# SpaceInvaders-OtherMill-BottomOnly.net
KiCad netlist of a schematic drawn in EAGLE
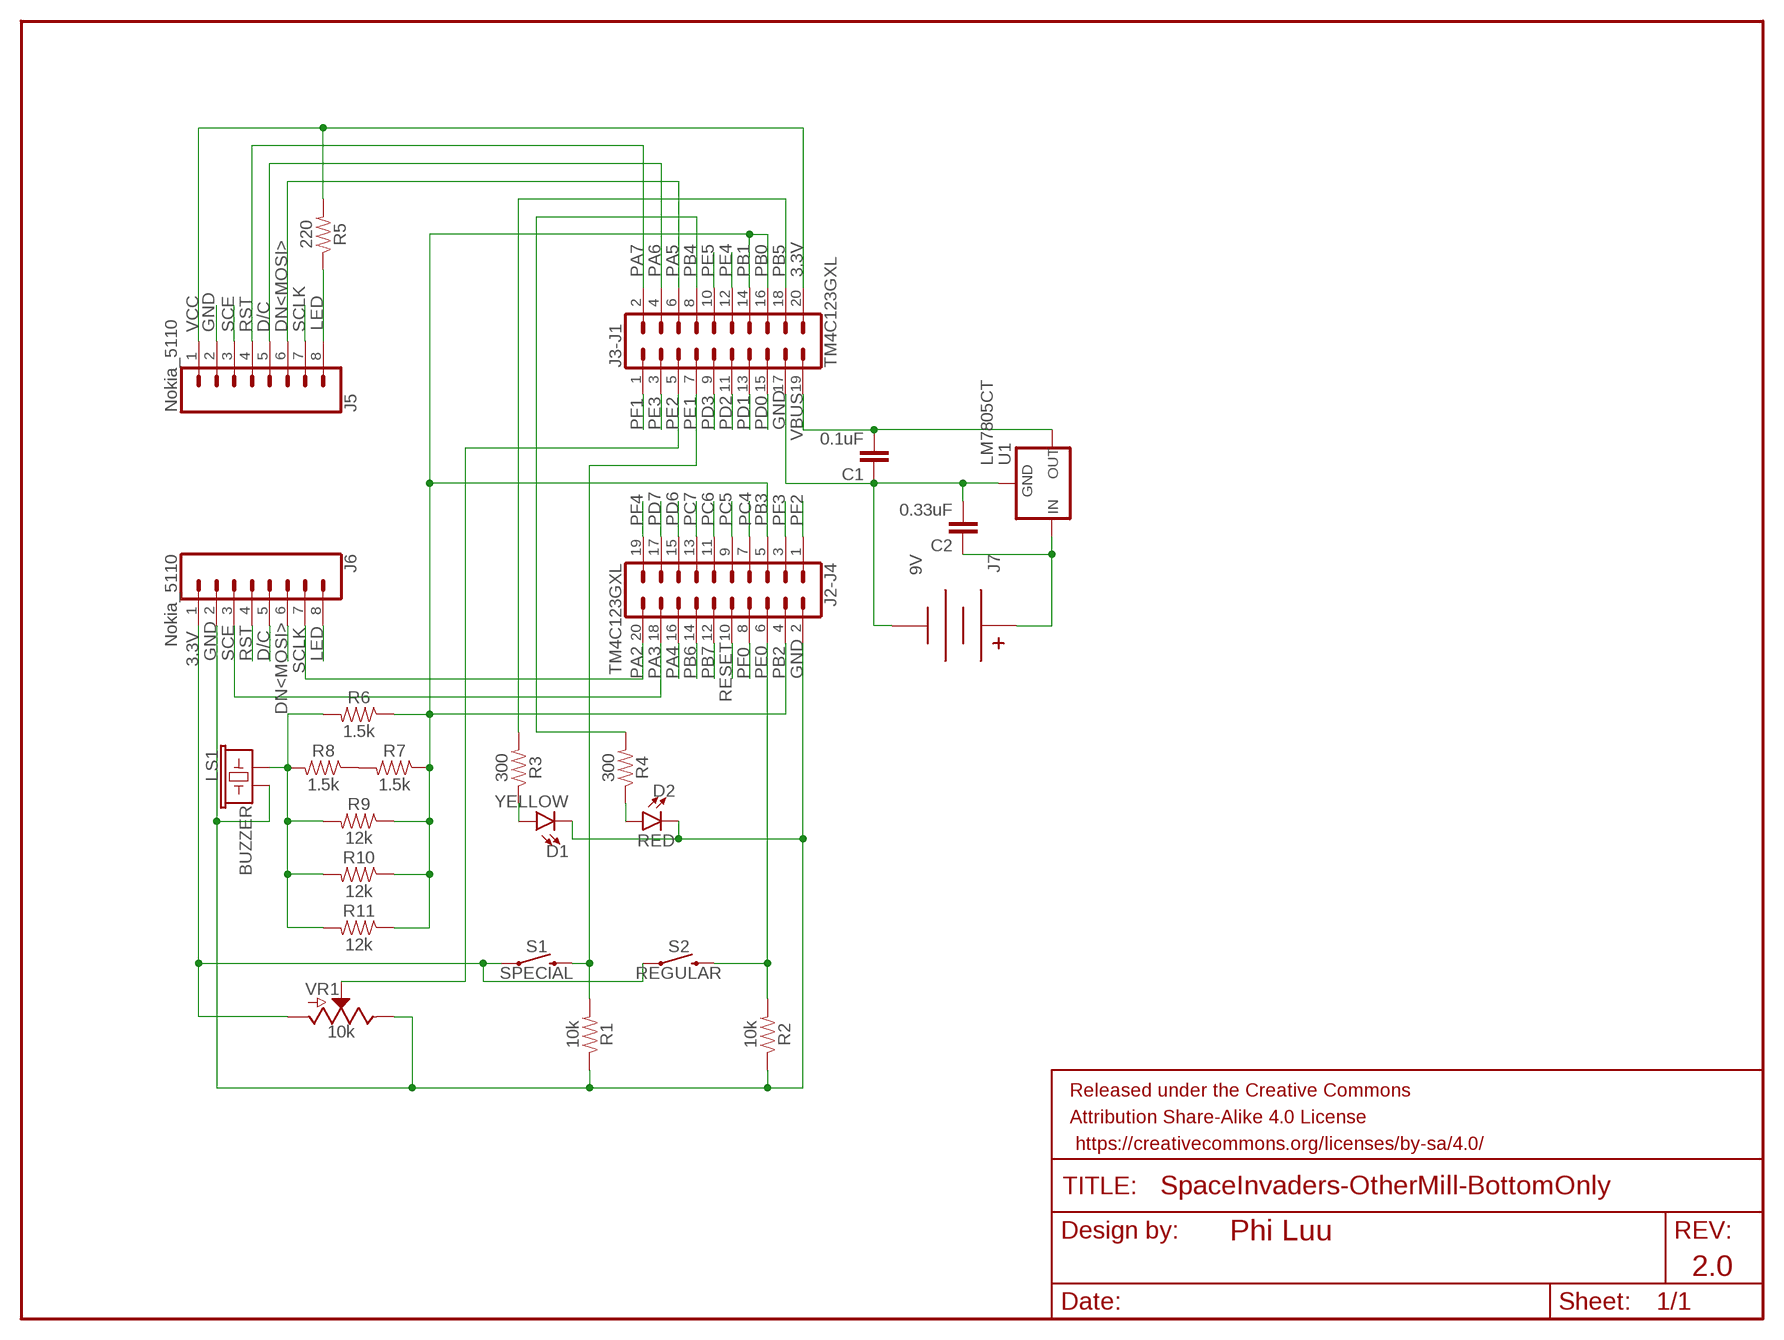
[diagram p0: schematic, sheet 1]

(export (version "E")
  (design (tool "Eeschema 10.0.6"))
  (components
    (comp (ref "C1")
      (value "0.1uF")
      (footprint "eagle-import:CAP-PTH-SMALL-KIT")
      (libsource (lib "eagle-import") (part "0.1UF-KIT-EZ-50V-20%"))
    )
    (comp (ref "C2")
      (value "0.33uF")
      (footprint "eagle-import:CAP-PTH-SMALL-KIT")
      (libsource (lib "eagle-import") (part "0.1UF-KIT-EZ-50V-20%"))
    )
    (comp (ref "D1")
      (value "YELLOW")
      (footprint "eagle-import:LED_5MM")
      (libsource (lib "eagle-import") (part "LED5MM"))
    )
    (comp (ref "D2")
      (value "RED")
      (footprint "eagle-import:LED_5MM")
      (libsource (lib "eagle-import") (part "LED5MM"))
    )
    (comp (ref "FRAME1")
      (value "FRAME-LETTER")
      (footprint "eagle-import:CREATIVE_COMMONS")
      (libsource (lib "eagle-import") (part "FRAME-LETTER"))
    )
    (comp (ref "J2-J4")
      (value "TM4C123GXL")
      (footprint "eagle-import:2X10")
      (libsource (lib "eagle-import") (part "CONN_10X2"))
    )
    (comp (ref "J3-J1")
      (value "TM4C123GXL")
      (footprint "eagle-import:2X10")
      (libsource (lib "eagle-import") (part "CONN_10X2"))
    )
    (comp (ref "J5")
      (value "Nokia_5110")
      (footprint "eagle-import:1X08")
      (libsource (lib "eagle-import") (part "CONN_08{dblquote}"))
    )
    (comp (ref "J6")
      (value "Nokia_5110")
      (footprint "eagle-import:1X08")
      (libsource (lib "eagle-import") (part "CONN_08{dblquote}"))
    )
    (comp (ref "J7")
      (value "9V")
      (footprint "eagle-import:BC9VPC")
      (libsource (lib "eagle-import") (part "BC9VPC"))
    )
    (comp (ref "LS1")
      (value "BUZZER")
      (footprint "eagle-import:BUZZER-12MM")
      (libsource (lib "eagle-import") (part "BUZZER-PTH"))
    )
    (comp (ref "R1")
      (value "10k")
      (footprint "eagle-import:AXIAL-0.3")
      (libsource (lib "eagle-import") (part "10KOHM-HORIZ-1/4W-5%"))
    )
    (comp (ref "R2")
      (value "10k")
      (footprint "eagle-import:AXIAL-0.3")
      (libsource (lib "eagle-import") (part "10KOHM-HORIZ-1/4W-5%"))
    )
    (comp (ref "R3")
      (value "300")
      (footprint "eagle-import:AXIAL-0.3")
      (libsource (lib "eagle-import") (part "1KOHM-HORIZ-1/4W-5%"))
    )
    (comp (ref "R4")
      (value "300")
      (footprint "eagle-import:AXIAL-0.3")
      (libsource (lib "eagle-import") (part "1KOHM-HORIZ-1/4W-5%"))
    )
    (comp (ref "R5")
      (value "220")
      (footprint "eagle-import:AXIAL-0.3")
      (libsource (lib "eagle-import") (part "1KOHM-HORIZ-1/4W-5%"))
    )
    (comp (ref "R6")
      (value "1.5k")
      (footprint "eagle-import:AXIAL-0.3")
      (libsource (lib "eagle-import") (part "1KOHM-HORIZ-1/4W-5%"))
    )
    (comp (ref "R7")
      (value "1.5k")
      (footprint "eagle-import:AXIAL-0.3")
      (libsource (lib "eagle-import") (part "1KOHM-HORIZ-1/4W-5%"))
    )
    (comp (ref "R8")
      (value "1.5k")
      (footprint "eagle-import:AXIAL-0.3")
      (libsource (lib "eagle-import") (part "1KOHM-HORIZ-1/4W-5%"))
    )
    (comp (ref "R9")
      (value "12k")
      (footprint "eagle-import:AXIAL-0.3")
      (libsource (lib "eagle-import") (part "1KOHM-HORIZ-1/4W-5%"))
    )
    (comp (ref "R10")
      (value "12k")
      (footprint "eagle-import:AXIAL-0.3")
      (libsource (lib "eagle-import") (part "1KOHM-HORIZ-1/4W-5%"))
    )
    (comp (ref "R11")
      (value "12k")
      (footprint "eagle-import:AXIAL-0.3")
      (libsource (lib "eagle-import") (part "1KOHM-HORIZ-1/4W-5%"))
    )
    (comp (ref "S1")
      (value "SPECIAL")
      (footprint "eagle-import:TACTILE_SWITCH_PTH_6.0MM")
      (libsource (lib "eagle-import") (part "MOMENTARY-SWITCH-SPST-PTH-6.0MM"))
    )
    (comp (ref "S2")
      (value "REGULAR")
      (footprint "eagle-import:TACTILE_SWITCH_PTH_6.0MM")
      (libsource (lib "eagle-import") (part "MOMENTARY-SWITCH-SPST-PTH-6.0MM"))
    )
    (comp (ref "U1")
      (value "LM7805CT")
      (footprint "eagle-import:TO-220-ALT")
      (libsource (lib "eagle-import") (part "V_REG_78XX-TO-220"))
    )
    (comp (ref "VR1")
      (value "10k")
      (footprint "eagle-import:SLIDER-MEDIUM")
      (libsource (lib "eagle-import") (part "POTENTIOMETER_SLIDE-30MM-1/10W-20%"))
    )
  )
  (nets
    (net (code "1") (name "/3.3V") (class "Default")
      (node (ref "J3-J1") (pin "20") (pinfunction "20_20") (pintype "passive"))
      (node (ref "J5") (pin "1") (pinfunction "1_1") (pintype "passive"))
      (node (ref "J6") (pin "1") (pinfunction "1_1") (pintype "passive"))
      (node (ref "R5") (pin "P$2") (pinfunction "2_P$2") (pintype "passive"))
      (node (ref "S1") (pin "1") (pinfunction "1_1") (pintype "passive"))
      (node (ref "S2") (pin "1") (pinfunction "1_1") (pintype "passive"))
      (node (ref "VR1") (pin "BOTTOM") (pinfunction "A_BOTTOM") (pintype "passive"))
    )
    (net (code "2") (name "/DN<MOSI>") (class "Default")
      (node (ref "J6") (pin "6") (pinfunction "6_6") (pintype "passive"))
    )
    (net (code "3") (name "/D{slash}C") (class "Default")
      (node (ref "J6") (pin "5") (pinfunction "5_5") (pintype "passive"))
    )
    (net (code "4") (name "/GND") (class "Default")
      (node (ref "C1") (pin "1") (pinfunction "1_1") (pintype "passive"))
      (node (ref "C2") (pin "2") (pinfunction "2_2") (pintype "passive"))
      (node (ref "D1") (pin "K") (pinfunction "C_K") (pintype "passive"))
      (node (ref "D2") (pin "K") (pinfunction "C_K") (pintype "passive"))
      (node (ref "J2-J4") (pin "2") (pinfunction "2_2") (pintype "passive"))
      (node (ref "J3-J1") (pin "17") (pinfunction "17_17") (pintype "passive"))
      (node (ref "J5") (pin "2") (pinfunction "2_2") (pintype "passive"))
      (node (ref "J6") (pin "2") (pinfunction "2_2") (pintype "passive"))
      (node (ref "J7") (pin "V-") (pinfunction "V-_V-") (pintype "bidirectional"))
      (node (ref "LS1") (pin "-") (pinfunction "2_-") (pintype "passive"))
      (node (ref "R1") (pin "P$1") (pinfunction "1_P$1") (pintype "passive"))
      (node (ref "R2") (pin "P$1") (pinfunction "1_P$1") (pintype "passive"))
      (node (ref "U1") (pin "GND") (pinfunction "GND_GND") (pintype "input"))
      (node (ref "VR1") (pin "TOP") (pinfunction "E_TOP") (pintype "passive"))
    )
    (net (code "5") (name "/LED") (class "Default")
      (node (ref "J5") (pin "8") (pinfunction "8_8") (pintype "passive"))
      (node (ref "J6") (pin "8") (pinfunction "8_8") (pintype "passive"))
      (node (ref "R5") (pin "P$1") (pinfunction "1_P$1") (pintype "passive"))
    )
    (net (code "6") (name "/PA2") (class "Default")
      (node (ref "J2-J4") (pin "20") (pinfunction "20_20") (pintype "passive"))
      (node (ref "J6") (pin "7") (pinfunction "7_7") (pintype "passive"))
    )
    (net (code "7") (name "/PA3") (class "Default")
      (node (ref "J2-J4") (pin "18") (pinfunction "18_18") (pintype "passive"))
      (node (ref "J6") (pin "3") (pinfunction "3_3") (pintype "passive"))
    )
    (net (code "8") (name "/PA4") (class "Default")
      (node (ref "J2-J4") (pin "16") (pinfunction "16_16") (pintype "passive"))
    )
    (net (code "9") (name "/PA5") (class "Default")
      (node (ref "J3-J1") (pin "6") (pinfunction "6_6") (pintype "passive"))
      (node (ref "J5") (pin "6") (pinfunction "6_6") (pintype "passive"))
    )
    (net (code "10") (name "/PA6") (class "Default")
      (node (ref "J3-J1") (pin "4") (pinfunction "4_4") (pintype "passive"))
      (node (ref "J5") (pin "5") (pinfunction "5_5") (pintype "passive"))
    )
    (net (code "11") (name "/PA7") (class "Default")
      (node (ref "J3-J1") (pin "2") (pinfunction "2_2") (pintype "passive"))
      (node (ref "J5") (pin "4") (pinfunction "4_4") (pintype "passive"))
    )
    (net (code "12") (name "/PB2") (class "Default")
      (node (ref "J2-J4") (pin "4") (pinfunction "4_4") (pintype "passive"))
      (node (ref "J2-J4") (pin "5") (pinfunction "5_5") (pintype "passive"))
      (node (ref "J3-J1") (pin "14") (pinfunction "14_14") (pintype "passive"))
      (node (ref "J3-J1") (pin "16") (pinfunction "16_16") (pintype "passive"))
      (node (ref "R10") (pin "P$1") (pinfunction "1_P$1") (pintype "passive"))
      (node (ref "R11") (pin "P$1") (pinfunction "1_P$1") (pintype "passive"))
      (node (ref "R6") (pin "P$1") (pinfunction "1_P$1") (pintype "passive"))
      (node (ref "R7") (pin "P$1") (pinfunction "1_P$1") (pintype "passive"))
      (node (ref "R9") (pin "P$1") (pinfunction "1_P$1") (pintype "passive"))
    )
    (net (code "13") (name "/PB4") (class "Default")
      (node (ref "J3-J1") (pin "8") (pinfunction "8_8") (pintype "passive"))
      (node (ref "R4") (pin "P$2") (pinfunction "2_P$2") (pintype "passive"))
    )
    (net (code "14") (name "/PB5") (class "Default")
      (node (ref "J3-J1") (pin "18") (pinfunction "18_18") (pintype "passive"))
      (node (ref "R3") (pin "P$2") (pinfunction "2_P$2") (pintype "passive"))
    )
    (net (code "15") (name "/PB6") (class "Default")
      (node (ref "J2-J4") (pin "14") (pinfunction "14_14") (pintype "passive"))
    )
    (net (code "16") (name "/PB7") (class "Default")
      (node (ref "J2-J4") (pin "12") (pinfunction "12_12") (pintype "passive"))
    )
    (net (code "17") (name "/PC4") (class "Default")
      (node (ref "J2-J4") (pin "7") (pinfunction "7_7") (pintype "passive"))
    )
    (net (code "18") (name "/PC5") (class "Default")
      (node (ref "J2-J4") (pin "9") (pinfunction "9_9") (pintype "passive"))
    )
    (net (code "19") (name "/PC6") (class "Default")
      (node (ref "J2-J4") (pin "11") (pinfunction "11_11") (pintype "passive"))
    )
    (net (code "20") (name "/PC7") (class "Default")
      (node (ref "J2-J4") (pin "13") (pinfunction "13_13") (pintype "passive"))
    )
    (net (code "21") (name "/PD0") (class "Default")
      (node (ref "J3-J1") (pin "15") (pinfunction "15_15") (pintype "passive"))
    )
    (net (code "22") (name "/PD1") (class "Default")
      (node (ref "J3-J1") (pin "13") (pinfunction "13_13") (pintype "passive"))
    )
    (net (code "23") (name "/PD2") (class "Default")
      (node (ref "J3-J1") (pin "11") (pinfunction "11_11") (pintype "passive"))
    )
    (net (code "24") (name "/PD3") (class "Default")
      (node (ref "J3-J1") (pin "9") (pinfunction "9_9") (pintype "passive"))
    )
    (net (code "25") (name "/PD6") (class "Default")
      (node (ref "J2-J4") (pin "15") (pinfunction "15_15") (pintype "passive"))
    )
    (net (code "26") (name "/PD7") (class "Default")
      (node (ref "J2-J4") (pin "17") (pinfunction "17_17") (pintype "passive"))
    )
    (net (code "27") (name "/PE0") (class "Default")
      (node (ref "J2-J4") (pin "6") (pinfunction "6_6") (pintype "passive"))
      (node (ref "R2") (pin "P$2") (pinfunction "2_P$2") (pintype "passive"))
      (node (ref "S2") (pin "3") (pinfunction "2_3") (pintype "passive"))
    )
    (net (code "28") (name "/PE1") (class "Default")
      (node (ref "J3-J1") (pin "7") (pinfunction "7_7") (pintype "passive"))
      (node (ref "R1") (pin "P$2") (pinfunction "2_P$2") (pintype "passive"))
      (node (ref "S1") (pin "3") (pinfunction "2_3") (pintype "passive"))
    )
    (net (code "29") (name "/PE2") (class "Default")
      (node (ref "J3-J1") (pin "5") (pinfunction "5_5") (pintype "passive"))
      (node (ref "VR1") (pin "WIPER") (pinfunction "S_WIPER") (pintype "passive"))
    )
    (net (code "30") (name "/PE3") (class "Default")
      (node (ref "J3-J1") (pin "3") (pinfunction "3_3") (pintype "passive"))
    )
    (net (code "31") (name "/PE4") (class "Default")
      (node (ref "J3-J1") (pin "12") (pinfunction "12_12") (pintype "passive"))
    )
    (net (code "32") (name "/PE5") (class "Default")
      (node (ref "J3-J1") (pin "10") (pinfunction "10_10") (pintype "passive"))
    )
    (net (code "33") (name "/PF0") (class "Default")
      (node (ref "J2-J4") (pin "8") (pinfunction "8_8") (pintype "passive"))
    )
    (net (code "34") (name "/PF1") (class "Default")
      (node (ref "J3-J1") (pin "1") (pinfunction "1_1") (pintype "passive"))
    )
    (net (code "35") (name "/PF2") (class "Default")
      (node (ref "J2-J4") (pin "1") (pinfunction "1_1") (pintype "passive"))
    )
    (net (code "36") (name "/PF3") (class "Default")
      (node (ref "J2-J4") (pin "3") (pinfunction "3_3") (pintype "passive"))
    )
    (net (code "37") (name "/PF4") (class "Default")
      (node (ref "J2-J4") (pin "19") (pinfunction "19_19") (pintype "passive"))
    )
    (net (code "38") (name "/RESET") (class "Default")
      (node (ref "J2-J4") (pin "10") (pinfunction "10_10") (pintype "passive"))
    )
    (net (code "39") (name "/RST") (class "Default")
      (node (ref "J6") (pin "4") (pinfunction "4_4") (pintype "passive"))
    )
    (net (code "40") (name "/SCE") (class "Default")
      (node (ref "J5") (pin "3") (pinfunction "3_3") (pintype "passive"))
    )
    (net (code "41") (name "/SCLK") (class "Default")
      (node (ref "J5") (pin "7") (pinfunction "7_7") (pintype "passive"))
    )
    (net (code "42") (name "/VBUS") (class "Default")
      (node (ref "C1") (pin "2") (pinfunction "2_2") (pintype "passive"))
      (node (ref "J3-J1") (pin "19") (pinfunction "19_19") (pintype "passive"))
      (node (ref "U1") (pin "OUT") (pinfunction "OUT_OUT") (pintype "passive"))
    )
    (net (code "43") (name "Net-(C2-Pad1)") (class "Default")
      (node (ref "C2") (pin "1") (pinfunction "1_1") (pintype "passive"))
      (node (ref "J7") (pin "V+") (pinfunction "V+_V+") (pintype "bidirectional"))
      (node (ref "U1") (pin "IN") (pinfunction "IN_IN") (pintype "input"))
    )
    (net (code "44") (name "Net-(LS1-1)") (class "Default")
      (node (ref "LS1") (pin "+") (pinfunction "1_+") (pintype "passive"))
      (node (ref "R10") (pin "P$2") (pinfunction "2_P$2") (pintype "passive"))
      (node (ref "R11") (pin "P$2") (pinfunction "2_P$2") (pintype "passive"))
      (node (ref "R6") (pin "P$2") (pinfunction "2_P$2") (pintype "passive"))
      (node (ref "R8") (pin "P$2") (pinfunction "2_P$2") (pintype "passive"))
      (node (ref "R9") (pin "P$2") (pinfunction "2_P$2") (pintype "passive"))
    )
    (net (code "45") (name "Net-(R3-1)") (class "Default")
      (node (ref "D1") (pin "A") (pinfunction "A_A") (pintype "passive"))
      (node (ref "R3") (pin "P$1") (pinfunction "1_P$1") (pintype "passive"))
    )
    (net (code "46") (name "Net-(R4-1)") (class "Default")
      (node (ref "D2") (pin "A") (pinfunction "A_A") (pintype "passive"))
      (node (ref "R4") (pin "P$1") (pinfunction "1_P$1") (pintype "passive"))
    )
    (net (code "47") (name "Net-(R7-2)") (class "Default")
      (node (ref "R7") (pin "P$2") (pinfunction "2_P$2") (pintype "passive"))
      (node (ref "R8") (pin "P$1") (pinfunction "1_P$1") (pintype "passive"))
    )
  )
)
